# shield_v5.net
KiCad netlist of a schematic drawn in EAGLE
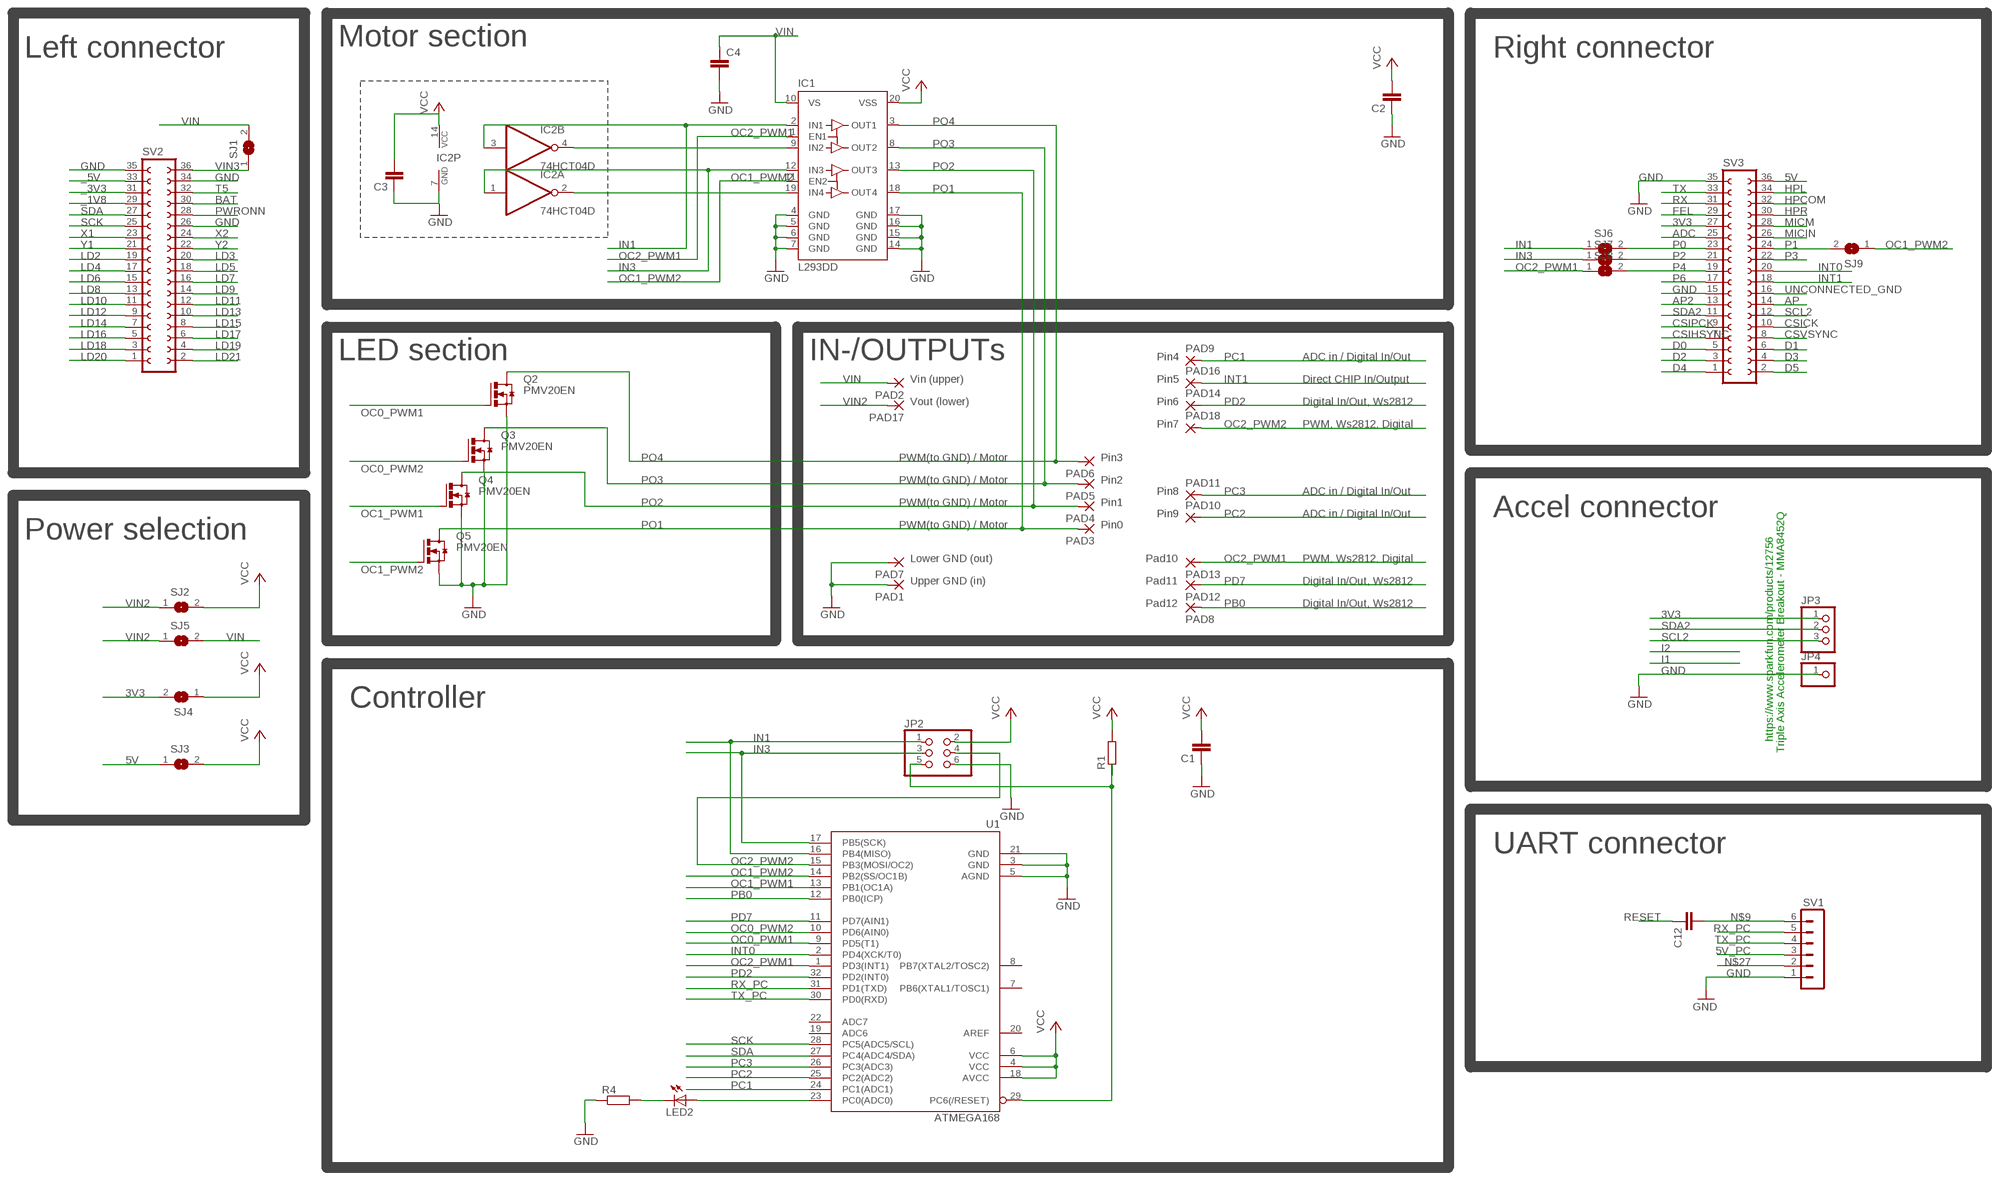
[diagram p0: schematic, sheet 1]

(export (version "E")
  (design (tool "Eeschema 10.0.6"))
  (components
    (comp (ref "C1")
      (value "C-EUC0805")
      (footprint "eagle-import:C0805")
      (libsource (lib "eagle-import") (part "C-EUC0805"))
    )
    (comp (ref "C2")
      (value "C-EUC0805")
      (footprint "eagle-import:C0805")
      (libsource (lib "eagle-import") (part "C-EUC0805"))
    )
    (comp (ref "C3")
      (value "C-EUC0805")
      (footprint "eagle-import:C0805")
      (libsource (lib "eagle-import") (part "C-EUC0805"))
    )
    (comp (ref "C4")
      (value "C-EUC1210")
      (footprint "eagle-import:C1210")
      (libsource (lib "eagle-import") (part "C-EUC1210"))
    )
    (comp (ref "C12")
      (value "C-EUC1206")
      (footprint "eagle-import:C1206")
      (libsource (lib "eagle-import") (part "C-EUC1206"))
    )
    (comp (ref "IC1")
      (value "L293DD")
      (footprint "eagle-import:SO20")
      (libsource (lib "eagle-import") (part "L293DD"))
    )
    (comp (ref "IC2")
      (value "74HCT04D")
      (footprint "eagle-import:SO14")
      (libsource (lib "eagle-import") (part "7404DHCT"))
    )
    (comp (ref "JP2")
      (value "PINHD-2X3")
      (footprint "eagle-import:2X03")
      (libsource (lib "eagle-import") (part "PINHD-2X3"))
    )
    (comp (ref "JP3")
      (value "PINHD-1X3")
      (footprint "eagle-import:1X03")
      (libsource (lib "eagle-import") (part "PINHD-1X3"))
    )
    (comp (ref "JP4")
      (value "PINHD-1X1")
      (footprint "eagle-import:1X01")
      (libsource (lib "eagle-import") (part "PINHD-1X1"))
    )
    (comp (ref "LED2")
      (value "LEDCHIP-LED0805")
      (footprint "eagle-import:CHIP-LED0805")
      (libsource (lib "eagle-import") (part "LEDCHIP-LED0805"))
    )
    (comp (ref "PAD1")
      (value "3,17/1,3")
      (footprint "eagle-import:3,17_1,3")
      (libsource (lib "eagle-import") (part "3,17/1,3"))
    )
    (comp (ref "PAD2")
      (value "3,17/1,3")
      (footprint "eagle-import:3,17_1,3")
      (libsource (lib "eagle-import") (part "3,17/1,3"))
    )
    (comp (ref "PAD3")
      (value "3,17/1,3")
      (footprint "eagle-import:3,17_1,3")
      (libsource (lib "eagle-import") (part "3,17/1,3"))
    )
    (comp (ref "PAD4")
      (value "3,17/1,3")
      (footprint "eagle-import:3,17_1,3")
      (libsource (lib "eagle-import") (part "3,17/1,3"))
    )
    (comp (ref "PAD5")
      (value "3,17/1,3")
      (footprint "eagle-import:3,17_1,3")
      (libsource (lib "eagle-import") (part "3,17/1,3"))
    )
    (comp (ref "PAD6")
      (value "3,17/1,3")
      (footprint "eagle-import:3,17_1,3")
      (libsource (lib "eagle-import") (part "3,17/1,3"))
    )
    (comp (ref "PAD7")
      (value "3,17/1,3")
      (footprint "eagle-import:3,17_1,3")
      (libsource (lib "eagle-import") (part "3,17/1,3"))
    )
    (comp (ref "PAD8")
      (value "WIREPADSMD1,27-254")
      (footprint "eagle-import:SMD1,27-2,54")
      (libsource (lib "eagle-import") (part "WIREPADSMD1,27-254"))
    )
    (comp (ref "PAD9")
      (value "3,17/1,3")
      (footprint "eagle-import:3,17_1,3")
      (libsource (lib "eagle-import") (part "3,17/1,3"))
    )
    (comp (ref "PAD10")
      (value "3,17/1,3")
      (footprint "eagle-import:3,17_1,3")
      (libsource (lib "eagle-import") (part "3,17/1,3"))
    )
    (comp (ref "PAD11")
      (value "3,17/1,3")
      (footprint "eagle-import:3,17_1,3")
      (libsource (lib "eagle-import") (part "3,17/1,3"))
    )
    (comp (ref "PAD12")
      (value "SMD2")
      (footprint "eagle-import:SMD1,27-2,54")
      (libsource (lib "eagle-import") (part "SMD2"))
    )
    (comp (ref "PAD13")
      (value "SMD2")
      (footprint "eagle-import:SMD1,27-2,54")
      (libsource (lib "eagle-import") (part "SMD2"))
    )
    (comp (ref "PAD14")
      (value "3,17/1,3")
      (footprint "eagle-import:3,17_1,3")
      (libsource (lib "eagle-import") (part "3,17/1,3"))
    )
    (comp (ref "PAD16")
      (value "3,17/1,3")
      (footprint "eagle-import:3,17_1,3")
      (libsource (lib "eagle-import") (part "3,17/1,3"))
    )
    (comp (ref "PAD17")
      (value "3,17/1,3")
      (footprint "eagle-import:3,17_1,3")
      (libsource (lib "eagle-import") (part "3,17/1,3"))
    )
    (comp (ref "PAD18")
      (value "3,17/1,3")
      (footprint "eagle-import:3,17_1,3")
      (libsource (lib "eagle-import") (part "3,17/1,3"))
    )
    (comp (ref "Q2")
      (value "PMV20EN")
      (footprint "eagle-import:SOT223")
      (libsource (lib "eagle-import") (part "NMOSFET_SMD_223"))
    )
    (comp (ref "Q3")
      (value "PMV20EN")
      (footprint "eagle-import:SOT223")
      (libsource (lib "eagle-import") (part "NMOSFET_SMD_223"))
    )
    (comp (ref "Q4")
      (value "PMV20EN")
      (footprint "eagle-import:SOT223")
      (libsource (lib "eagle-import") (part "NMOSFET_SMD_223"))
    )
    (comp (ref "Q5")
      (value "PMV20EN")
      (footprint "eagle-import:SOT223")
      (libsource (lib "eagle-import") (part "NMOSFET_SMD_223"))
    )
    (comp (ref "R1")
      (value "R-EU_M1206")
      (footprint "eagle-import:M1206")
      (libsource (lib "eagle-import") (part "R-EU_M1206"))
    )
    (comp (ref "R4")
      (value "R-EU_M1206")
      (footprint "eagle-import:M1206")
      (libsource (lib "eagle-import") (part "R-EU_M1206"))
    )
    (comp (ref "SJ1") (value "SJ") (footprint "eagle-import:SJ") (libsource (lib "eagle-import") (part "SJ")))
    (comp (ref "SJ2") (value "SJ") (footprint "eagle-import:SJ") (libsource (lib "eagle-import") (part "SJ")))
    (comp (ref "SJ3") (value "SJ") (footprint "eagle-import:SJ") (libsource (lib "eagle-import") (part "SJ")))
    (comp (ref "SJ4") (value "SJ") (footprint "eagle-import:SJ") (libsource (lib "eagle-import") (part "SJ")))
    (comp (ref "SJ5") (value "SJ") (footprint "eagle-import:SJ") (libsource (lib "eagle-import") (part "SJ")))
    (comp (ref "SJ6") (value "SJ") (footprint "eagle-import:SJ") (libsource (lib "eagle-import") (part "SJ")))
    (comp (ref "SJ7") (value "SJ") (footprint "eagle-import:SJ") (libsource (lib "eagle-import") (part "SJ")))
    (comp (ref "SJ8") (value "SJ") (footprint "eagle-import:SJ") (libsource (lib "eagle-import") (part "SJ")))
    (comp (ref "SJ9") (value "SJ") (footprint "eagle-import:SJ") (libsource (lib "eagle-import") (part "SJ")))
    (comp (ref "SV1")
      (value "MA06-1")
      (footprint "eagle-import:MA06-1")
      (libsource (lib "eagle-import") (part "MA06-1"))
    )
    (comp (ref "SV2")
      (value "FE18-2")
      (footprint "eagle-import:FE18-2")
      (libsource (lib "eagle-import") (part "FE18-2"))
    )
    (comp (ref "SV3")
      (value "FE18-2")
      (footprint "eagle-import:FE18-2")
      (libsource (lib "eagle-import") (part "FE18-2"))
    )
    (comp (ref "U1")
      (value "ATMEGA168")
      (footprint "eagle-import:TQFP32-08")
      (libsource (lib "eagle-import") (part "ATMEGA168"))
    )
  )
  (nets
    (net (code "1") (name "/3V3") (class "Default")
      (node (ref "JP3") (pin "1") (pinfunction "1_1") (pintype "passive"))
      (node (ref "SJ4") (pin "2") (pinfunction "2_2") (pintype "passive"))
      (node (ref "SV3") (pin "27") (pinfunction "27_27") (pintype "passive"))
    )
    (net (code "2") (name "/5V") (class "Default")
      (node (ref "SJ3") (pin "1") (pinfunction "1_1") (pintype "passive"))
      (node (ref "SV3") (pin "36") (pinfunction "36_36") (pintype "passive"))
    )
    (net (code "3") (name "/5V_PC") (class "Default")
      (node (ref "SV1") (pin "3") (pinfunction "3_3") (pintype "passive"))
    )
    (net (code "4") (name "/ADC") (class "Default")
      (node (ref "SV3") (pin "25") (pinfunction "25_25") (pintype "passive"))
    )
    (net (code "5") (name "/AP") (class "Default")
      (node (ref "SV3") (pin "14") (pinfunction "14_14") (pintype "passive"))
    )
    (net (code "6") (name "/AP2") (class "Default")
      (node (ref "SV3") (pin "13") (pinfunction "13_13") (pintype "passive"))
    )
    (net (code "7") (name "/BAT") (class "Default")
      (node (ref "SV2") (pin "30") (pinfunction "30_30") (pintype "passive"))
    )
    (net (code "8") (name "/CSICK") (class "Default")
      (node (ref "SV3") (pin "10") (pinfunction "10_10") (pintype "passive"))
    )
    (net (code "9") (name "/CSIHSYNC") (class "Default")
      (node (ref "SV3") (pin "7") (pinfunction "7_7") (pintype "passive"))
    )
    (net (code "10") (name "/CSIPCK") (class "Default")
      (node (ref "SV3") (pin "9") (pinfunction "9_9") (pintype "passive"))
    )
    (net (code "11") (name "/CSVSYNC") (class "Default")
      (node (ref "SV3") (pin "8") (pinfunction "8_8") (pintype "passive"))
    )
    (net (code "12") (name "/D0") (class "Default")
      (node (ref "SV3") (pin "5") (pinfunction "5_5") (pintype "passive"))
    )
    (net (code "13") (name "/D1") (class "Default")
      (node (ref "SV3") (pin "6") (pinfunction "6_6") (pintype "passive"))
    )
    (net (code "14") (name "/D2") (class "Default")
      (node (ref "SV3") (pin "3") (pinfunction "3_3") (pintype "passive"))
    )
    (net (code "15") (name "/D3") (class "Default")
      (node (ref "SV3") (pin "4") (pinfunction "4_4") (pintype "passive"))
    )
    (net (code "16") (name "/D4") (class "Default")
      (node (ref "SV3") (pin "1") (pinfunction "1_1") (pintype "passive"))
    )
    (net (code "17") (name "/D5") (class "Default")
      (node (ref "SV3") (pin "2") (pinfunction "2_2") (pintype "passive"))
    )
    (net (code "18") (name "/FEL") (class "Default")
      (node (ref "SV3") (pin "29") (pinfunction "29_29") (pintype "passive"))
    )
    (net (code "19") (name "/HPCOM") (class "Default")
      (node (ref "SV3") (pin "32") (pinfunction "32_32") (pintype "passive"))
    )
    (net (code "20") (name "/HPL") (class "Default")
      (node (ref "SV3") (pin "34") (pinfunction "34_34") (pintype "passive"))
    )
    (net (code "21") (name "/HPR") (class "Default")
      (node (ref "SV3") (pin "30") (pinfunction "30_30") (pintype "passive"))
    )
    (net (code "24") (name "/IN1") (class "Default")
      (node (ref "IC1") (pin "2") (pinfunction "IN1_2") (pintype "input"))
      (node (ref "IC2") (pin "3") (pinfunction "I_3") (pintype "input"))
      (node (ref "JP2") (pin "1") (pinfunction "1_1") (pintype "passive"))
      (node (ref "SJ6") (pin "1") (pinfunction "1_1") (pintype "passive"))
      (node (ref "U1") (pin "16") (pinfunction "PB4(MISO)_16") (pintype "bidirectional"))
    )
    (net (code "25") (name "/IN3") (class "Default")
      (node (ref "IC1") (pin "12") (pinfunction "IN3_12") (pintype "input"))
      (node (ref "IC2") (pin "1") (pinfunction "I_1") (pintype "input"))
      (node (ref "JP2") (pin "3") (pinfunction "3_3") (pintype "passive"))
      (node (ref "SJ7") (pin "1") (pinfunction "1_1") (pintype "passive"))
      (node (ref "U1") (pin "17") (pinfunction "PB5(SCK)_17") (pintype "bidirectional"))
    )
    (net (code "26") (name "/INT0") (class "Default")
      (node (ref "SV3") (pin "20") (pinfunction "20_20") (pintype "passive"))
      (node (ref "U1") (pin "2") (pinfunction "PD4(XCK/T0)_2") (pintype "bidirectional"))
    )
    (net (code "27") (name "/INT1") (class "Default")
      (node (ref "PAD16") (pin "1") (pinfunction "P_1") (pintype "passive"))
      (node (ref "SV3") (pin "18") (pinfunction "18_18") (pintype "passive"))
    )
    (net (code "28") (name "/LD2") (class "Default")
      (node (ref "SV2") (pin "19") (pinfunction "19_19") (pintype "passive"))
    )
    (net (code "29") (name "/LD3") (class "Default")
      (node (ref "SV2") (pin "20") (pinfunction "20_20") (pintype "passive"))
    )
    (net (code "30") (name "/LD4") (class "Default")
      (node (ref "SV2") (pin "17") (pinfunction "17_17") (pintype "passive"))
    )
    (net (code "31") (name "/LD5") (class "Default")
      (node (ref "SV2") (pin "18") (pinfunction "18_18") (pintype "passive"))
    )
    (net (code "32") (name "/LD6") (class "Default")
      (node (ref "SV2") (pin "15") (pinfunction "15_15") (pintype "passive"))
    )
    (net (code "33") (name "/LD7") (class "Default")
      (node (ref "SV2") (pin "16") (pinfunction "16_16") (pintype "passive"))
    )
    (net (code "34") (name "/LD8") (class "Default")
      (node (ref "SV2") (pin "13") (pinfunction "13_13") (pintype "passive"))
    )
    (net (code "35") (name "/LD9") (class "Default")
      (node (ref "SV2") (pin "14") (pinfunction "14_14") (pintype "passive"))
    )
    (net (code "36") (name "/LD10") (class "Default")
      (node (ref "SV2") (pin "11") (pinfunction "11_11") (pintype "passive"))
    )
    (net (code "37") (name "/LD11") (class "Default")
      (node (ref "SV2") (pin "12") (pinfunction "12_12") (pintype "passive"))
    )
    (net (code "38") (name "/LD12") (class "Default")
      (node (ref "SV2") (pin "9") (pinfunction "9_9") (pintype "passive"))
    )
    (net (code "39") (name "/LD13") (class "Default")
      (node (ref "SV2") (pin "10") (pinfunction "10_10") (pintype "passive"))
    )
    (net (code "40") (name "/LD14") (class "Default")
      (node (ref "SV2") (pin "7") (pinfunction "7_7") (pintype "passive"))
    )
    (net (code "41") (name "/LD15") (class "Default")
      (node (ref "SV2") (pin "8") (pinfunction "8_8") (pintype "passive"))
    )
    (net (code "42") (name "/LD16") (class "Default")
      (node (ref "SV2") (pin "5") (pinfunction "5_5") (pintype "passive"))
    )
    (net (code "43") (name "/LD17") (class "Default")
      (node (ref "SV2") (pin "6") (pinfunction "6_6") (pintype "passive"))
    )
    (net (code "44") (name "/LD18") (class "Default")
      (node (ref "SV2") (pin "3") (pinfunction "3_3") (pintype "passive"))
    )
    (net (code "45") (name "/LD19") (class "Default")
      (node (ref "SV2") (pin "4") (pinfunction "4_4") (pintype "passive"))
    )
    (net (code "46") (name "/LD20") (class "Default")
      (node (ref "SV2") (pin "1") (pinfunction "1_1") (pintype "passive"))
    )
    (net (code "47") (name "/LD21") (class "Default")
      (node (ref "SV2") (pin "2") (pinfunction "2_2") (pintype "passive"))
    )
    (net (code "48") (name "/MICIN") (class "Default")
      (node (ref "SV3") (pin "26") (pinfunction "26_26") (pintype "passive"))
    )
    (net (code "49") (name "/MICM") (class "Default")
      (node (ref "SV3") (pin "28") (pinfunction "28_28") (pintype "passive"))
    )
    (net (code "50") (name "/N$9") (class "Default")
      (node (ref "C12") (pin "2") (pinfunction "2_2") (pintype "passive"))
      (node (ref "SV1") (pin "6") (pinfunction "6_6") (pintype "passive"))
    )
    (net (code "51") (name "/N$27") (class "Default")
      (node (ref "SV1") (pin "2") (pinfunction "2_2") (pintype "passive"))
    )
    (net (code "52") (name "/OC0_PWM1") (class "Default")
      (node (ref "Q2") (pin "1") (pinfunction "G_1") (pintype "passive"))
      (node (ref "U1") (pin "9") (pinfunction "PD5(T1)_9") (pintype "bidirectional"))
    )
    (net (code "53") (name "/OC0_PWM2") (class "Default")
      (node (ref "Q3") (pin "1") (pinfunction "G_1") (pintype "passive"))
      (node (ref "U1") (pin "10") (pinfunction "PD6(AIN0)_10") (pintype "bidirectional"))
    )
    (net (code "54") (name "/OC1_PWM1") (class "Default")
      (node (ref "Q4") (pin "1") (pinfunction "G_1") (pintype "passive"))
      (node (ref "U1") (pin "13") (pinfunction "PB1(OC1A)_13") (pintype "bidirectional"))
    )
    (net (code "55") (name "/OC1_PWM2") (class "Default")
      (node (ref "IC1") (pin "11") (pinfunction "EN2_11") (pintype "input"))
      (node (ref "Q5") (pin "1") (pinfunction "G_1") (pintype "passive"))
      (node (ref "SJ9") (pin "1") (pinfunction "1_1") (pintype "passive"))
      (node (ref "U1") (pin "14") (pinfunction "PB2(SS/OC1B)_14") (pintype "bidirectional"))
    )
    (net (code "56") (name "/OC2_PWM1") (class "Default")
      (node (ref "IC1") (pin "1") (pinfunction "EN1_1") (pintype "input"))
      (node (ref "PAD13") (pin "1") (pinfunction "P_1") (pintype "passive"))
      (node (ref "SJ8") (pin "1") (pinfunction "1_1") (pintype "passive"))
      (node (ref "U1") (pin "1") (pinfunction "PD3(INT1)_1") (pintype "bidirectional"))
    )
    (net (code "57") (name "/OC2_PWM2") (class "Default")
      (node (ref "JP2") (pin "4") (pinfunction "4_4") (pintype "passive"))
      (node (ref "PAD18") (pin "1") (pinfunction "P_1") (pintype "passive"))
      (node (ref "U1") (pin "15") (pinfunction "PB3(MOSI/OC2)_15") (pintype "bidirectional"))
    )
    (net (code "58") (name "/P0") (class "Default")
      (node (ref "SJ6") (pin "2") (pinfunction "2_2") (pintype "passive"))
      (node (ref "SV3") (pin "23") (pinfunction "23_23") (pintype "passive"))
    )
    (net (code "59") (name "/P1") (class "Default")
      (node (ref "SJ9") (pin "2") (pinfunction "2_2") (pintype "passive"))
      (node (ref "SV3") (pin "24") (pinfunction "24_24") (pintype "passive"))
    )
    (net (code "60") (name "/P2") (class "Default")
      (node (ref "SJ7") (pin "2") (pinfunction "2_2") (pintype "passive"))
      (node (ref "SV3") (pin "21") (pinfunction "21_21") (pintype "passive"))
    )
    (net (code "61") (name "/P3") (class "Default")
      (node (ref "SV3") (pin "22") (pinfunction "22_22") (pintype "passive"))
    )
    (net (code "62") (name "/P4") (class "Default")
      (node (ref "SJ8") (pin "2") (pinfunction "2_2") (pintype "passive"))
      (node (ref "SV3") (pin "19") (pinfunction "19_19") (pintype "passive"))
    )
    (net (code "63") (name "/P6") (class "Default")
      (node (ref "SV3") (pin "17") (pinfunction "17_17") (pintype "passive"))
    )
    (net (code "64") (name "/PB0") (class "Default")
      (node (ref "PAD8") (pin "1") (pinfunction "P_1") (pintype "passive"))
      (node (ref "U1") (pin "12") (pinfunction "PB0(ICP)_12") (pintype "bidirectional"))
    )
    (net (code "65") (name "/PC1") (class "Default")
      (node (ref "PAD9") (pin "1") (pinfunction "P_1") (pintype "passive"))
      (node (ref "U1") (pin "24") (pinfunction "PC1(ADC1)_24") (pintype "bidirectional"))
    )
    (net (code "66") (name "/PC2") (class "Default")
      (node (ref "PAD10") (pin "1") (pinfunction "P_1") (pintype "passive"))
      (node (ref "U1") (pin "25") (pinfunction "PC2(ADC2)_25") (pintype "bidirectional"))
    )
    (net (code "67") (name "/PC3") (class "Default")
      (node (ref "PAD11") (pin "1") (pinfunction "P_1") (pintype "passive"))
      (node (ref "U1") (pin "26") (pinfunction "PC3(ADC3)_26") (pintype "bidirectional"))
    )
    (net (code "68") (name "/PD2") (class "Default")
      (node (ref "PAD14") (pin "1") (pinfunction "P_1") (pintype "passive"))
      (node (ref "U1") (pin "32") (pinfunction "PD2(INT0)_32") (pintype "bidirectional"))
    )
    (net (code "69") (name "/PD7") (class "Default")
      (node (ref "PAD12") (pin "1") (pinfunction "P_1") (pintype "passive"))
      (node (ref "U1") (pin "11") (pinfunction "PD7(AIN1)_11") (pintype "bidirectional"))
    )
    (net (code "70") (name "/PO1") (class "Default")
      (node (ref "IC1") (pin "18") (pinfunction "OUT4_18") (pintype "output"))
      (node (ref "PAD3") (pin "1") (pinfunction "P_1") (pintype "passive"))
      (node (ref "Q5") (pin "2") (pinfunction "D_2") (pintype "passive"))
      (node (ref "Q5") (pin "4") (pinfunction "D_4") (pintype "passive"))
    )
    (net (code "71") (name "/PO2") (class "Default")
      (node (ref "IC1") (pin "13") (pinfunction "OUT3_13") (pintype "output"))
      (node (ref "PAD4") (pin "1") (pinfunction "P_1") (pintype "passive"))
      (node (ref "Q4") (pin "2") (pinfunction "D_2") (pintype "passive"))
      (node (ref "Q4") (pin "4") (pinfunction "D_4") (pintype "passive"))
    )
    (net (code "72") (name "/PO3") (class "Default")
      (node (ref "IC1") (pin "8") (pinfunction "OUT2_8") (pintype "output"))
      (node (ref "PAD5") (pin "1") (pinfunction "P_1") (pintype "passive"))
      (node (ref "Q3") (pin "2") (pinfunction "D_2") (pintype "passive"))
      (node (ref "Q3") (pin "4") (pinfunction "D_4") (pintype "passive"))
    )
    (net (code "73") (name "/PO4") (class "Default")
      (node (ref "IC1") (pin "3") (pinfunction "OUT1_3") (pintype "output"))
      (node (ref "PAD6") (pin "1") (pinfunction "P_1") (pintype "passive"))
      (node (ref "Q2") (pin "2") (pinfunction "D_2") (pintype "passive"))
      (node (ref "Q2") (pin "4") (pinfunction "D_4") (pintype "passive"))
    )
    (net (code "74") (name "/PWRONN") (class "Default")
      (node (ref "SV2") (pin "28") (pinfunction "28_28") (pintype "passive"))
    )
    (net (code "75") (name "/RESET") (class "Default")
      (node (ref "C12") (pin "1") (pinfunction "1_1") (pintype "passive"))
      (node (ref "JP2") (pin "5") (pinfunction "5_5") (pintype "passive"))
      (node (ref "R1") (pin "1") (pinfunction "1_1") (pintype "passive"))
      (node (ref "U1") (pin "29") (pinfunction "PC6(/RESET)_29") (pintype "bidirectional"))
    )
    (net (code "76") (name "/RX") (class "Default")
      (node (ref "SV3") (pin "31") (pinfunction "31_31") (pintype "passive"))
    )
    (net (code "77") (name "/RX_PC") (class "Default")
      (node (ref "SV1") (pin "5") (pinfunction "5_5") (pintype "passive"))
      (node (ref "U1") (pin "31") (pinfunction "PD1(TXD)_31") (pintype "bidirectional"))
    )
    (net (code "78") (name "/SCK") (class "Default")
      (node (ref "SV2") (pin "25") (pinfunction "25_25") (pintype "passive"))
      (node (ref "U1") (pin "28") (pinfunction "PC5(ADC5/SCL)_28") (pintype "bidirectional"))
    )
    (net (code "79") (name "/SCL2") (class "Default")
      (node (ref "JP3") (pin "3") (pinfunction "3_3") (pintype "passive"))
      (node (ref "SV3") (pin "12") (pinfunction "12_12") (pintype "passive"))
    )
    (net (code "80") (name "/SDA") (class "Default")
      (node (ref "SV2") (pin "27") (pinfunction "27_27") (pintype "passive"))
      (node (ref "U1") (pin "27") (pinfunction "PC4(ADC4/SDA)_27") (pintype "bidirectional"))
    )
    (net (code "81") (name "/SDA2") (class "Default")
      (node (ref "JP3") (pin "2") (pinfunction "2_2") (pintype "passive"))
      (node (ref "SV3") (pin "11") (pinfunction "11_11") (pintype "passive"))
    )
    (net (code "82") (name "/T5") (class "Default")
      (node (ref "SV2") (pin "32") (pinfunction "32_32") (pintype "passive"))
    )
    (net (code "83") (name "/TX") (class "Default")
      (node (ref "SV3") (pin "33") (pinfunction "33_33") (pintype "passive"))
    )
    (net (code "84") (name "/TX_PC") (class "Default")
      (node (ref "SV1") (pin "4") (pinfunction "4_4") (pintype "passive"))
      (node (ref "U1") (pin "30") (pinfunction "PD0(RXD)_30") (pintype "bidirectional"))
    )
    (net (code "85") (name "/UNCONNECTED_GND") (class "Default")
      (node (ref "SV3") (pin "16") (pinfunction "16_16") (pintype "passive"))
    )
    (net (code "86") (name "/VIN") (class "Default")
      (node (ref "C4") (pin "1") (pinfunction "1_1") (pintype "passive"))
      (node (ref "IC1") (pin "10") (pinfunction "VS_10") (pintype "power_in"))
      (node (ref "PAD2") (pin "1") (pinfunction "P_1") (pintype "passive"))
      (node (ref "SJ1") (pin "2") (pinfunction "2_2") (pintype "passive"))
      (node (ref "SJ5") (pin "2") (pinfunction "2_2") (pintype "passive"))
    )
    (net (code "87") (name "/VIN2") (class "Default")
      (node (ref "PAD17") (pin "1") (pinfunction "P_1") (pintype "passive"))
      (node (ref "SJ2") (pin "1") (pinfunction "1_1") (pintype "passive"))
      (node (ref "SJ5") (pin "1") (pinfunction "1_1") (pintype "passive"))
    )
    (net (code "88") (name "/VIN3") (class "Default")
      (node (ref "SJ1") (pin "1") (pinfunction "1_1") (pintype "passive"))
      (node (ref "SV2") (pin "36") (pinfunction "36_36") (pintype "passive"))
    )
    (net (code "89") (name "/X1") (class "Default")
      (node (ref "SV2") (pin "23") (pinfunction "23_23") (pintype "passive"))
    )
    (net (code "90") (name "/X2") (class "Default")
      (node (ref "SV2") (pin "24") (pinfunction "24_24") (pintype "passive"))
    )
    (net (code "91") (name "/Y1") (class "Default")
      (node (ref "SV2") (pin "21") (pinfunction "21_21") (pintype "passive"))
    )
    (net (code "92") (name "/Y2") (class "Default")
      (node (ref "SV2") (pin "22") (pinfunction "22_22") (pintype "passive"))
    )
    (net (code "93") (name "/_1V8") (class "Default")
      (node (ref "SV2") (pin "29") (pinfunction "29_29") (pintype "passive"))
    )
    (net (code "94") (name "/_3V3") (class "Default")
      (node (ref "SV2") (pin "31") (pinfunction "31_31") (pintype "passive"))
    )
    (net (code "95") (name "/_5V") (class "Default")
      (node (ref "SV2") (pin "33") (pinfunction "33_33") (pintype "passive"))
    )
    (net (code "96") (name "GND") (class "Default")
      (node (ref "C1") (pin "1") (pinfunction "1_1") (pintype "passive"))
      (node (ref "C2") (pin "1") (pinfunction "1_1") (pintype "passive"))
      (node (ref "C3") (pin "1") (pinfunction "1_1") (pintype "passive"))
      (node (ref "C4") (pin "2") (pinfunction "2_2") (pintype "passive"))
      (node (ref "IC1") (pin "14") (pinfunction "GND_14") (pintype "power_in"))
      (node (ref "IC1") (pin "15") (pinfunction "GND_15") (pintype "power_in"))
      (node (ref "IC1") (pin "16") (pinfunction "GND_16") (pintype "power_in"))
      (node (ref "IC1") (pin "17") (pinfunction "GND_17") (pintype "power_in"))
      (node (ref "IC1") (pin "4") (pinfunction "GND_4") (pintype "power_in"))
      (node (ref "IC1") (pin "5") (pinfunction "GND_5") (pintype "power_in"))
      (node (ref "IC1") (pin "6") (pinfunction "GND_6") (pintype "power_in"))
      (node (ref "IC1") (pin "7") (pinfunction "GND_7") (pintype "power_in"))
      (node (ref "IC2") (pin "7") (pinfunction "GND_7") (pintype "power_in"))
      (node (ref "JP2") (pin "6") (pinfunction "6_6") (pintype "passive"))
      (node (ref "JP4") (pin "1") (pinfunction "1_1") (pintype "passive"))
      (node (ref "PAD1") (pin "1") (pinfunction "P_1") (pintype "passive"))
      (node (ref "PAD7") (pin "1") (pinfunction "P_1") (pintype "passive"))
      (node (ref "Q2") (pin "3") (pinfunction "S_3") (pintype "passive"))
      (node (ref "Q3") (pin "3") (pinfunction "S_3") (pintype "passive"))
      (node (ref "Q4") (pin "3") (pinfunction "S_3") (pintype "passive"))
      (node (ref "Q5") (pin "3") (pinfunction "S_3") (pintype "passive"))
      (node (ref "R4") (pin "1") (pinfunction "1_1") (pintype "passive"))
      (node (ref "SV1") (pin "1") (pinfunction "1_1") (pintype "passive"))
      (node (ref "SV2") (pin "26") (pinfunction "26_26") (pintype "passive"))
      (node (ref "SV2") (pin "34") (pinfunction "34_34") (pintype "passive"))
      (node (ref "SV2") (pin "35") (pinfunction "35_35") (pintype "passive"))
      (node (ref "SV3") (pin "15") (pinfunction "15_15") (pintype "passive"))
      (node (ref "SV3") (pin "35") (pinfunction "35_35") (pintype "passive"))
      (node (ref "U1") (pin "21") (pinfunction "GND_21") (pintype "bidirectional"))
      (node (ref "U1") (pin "3") (pinfunction "GND_3") (pintype "bidirectional"))
      (node (ref "U1") (pin "5") (pinfunction "AGND_5") (pintype "bidirectional"))
    )
    (net (code "97") (name "Net-(IC1-IN2)") (class "Default")
      (node (ref "IC1") (pin "9") (pinfunction "IN2_9") (pintype "input"))
      (node (ref "IC2") (pin "4") (pinfunction "O_4") (pintype "output"))
    )
    (net (code "98") (name "Net-(IC1-IN4)") (class "Default")
      (node (ref "IC1") (pin "19") (pinfunction "IN4_19") (pintype "input"))
      (node (ref "IC2") (pin "2") (pinfunction "O_2") (pintype "output"))
    )
    (net (code "99") (name "Net-(LED2-PadC)") (class "Default")
      (node (ref "LED2") (pin "C") (pinfunction "C_C") (pintype "passive"))
      (node (ref "R4") (pin "2") (pinfunction "2_2") (pintype "passive"))
    )
    (net (code "100") (name "Net-(U1-PC0(ADC0))") (class "Default")
      (node (ref "LED2") (pin "A") (pinfunction "A_A") (pintype "passive"))
      (node (ref "U1") (pin "23") (pinfunction "PC0(ADC0)_23") (pintype "bidirectional"))
    )
    (net (code "101") (name "VCC") (class "Default")
      (node (ref "C1") (pin "2") (pinfunction "2_2") (pintype "passive"))
      (node (ref "C2") (pin "2") (pinfunction "2_2") (pintype "passive"))
      (node (ref "C3") (pin "2") (pinfunction "2_2") (pintype "passive"))
      (node (ref "IC1") (pin "20") (pinfunction "VSS_20") (pintype "power_in"))
      (node (ref "IC2") (pin "14") (pinfunction "VCC_14") (pintype "power_in"))
      (node (ref "JP2") (pin "2") (pinfunction "2_2") (pintype "passive"))
      (node (ref "R1") (pin "2") (pinfunction "2_2") (pintype "passive"))
      (node (ref "SJ2") (pin "2") (pinfunction "2_2") (pintype "passive"))
      (node (ref "SJ3") (pin "2") (pinfunction "2_2") (pintype "passive"))
      (node (ref "SJ4") (pin "1") (pinfunction "1_1") (pintype "passive"))
      (node (ref "U1") (pin "18") (pinfunction "AVCC_18") (pintype "bidirectional"))
      (node (ref "U1") (pin "4") (pinfunction "VCC_4") (pintype "bidirectional"))
      (node (ref "U1") (pin "6") (pinfunction "VCC_6") (pintype "bidirectional"))
    )
    (net (code "102") (name "unconnected-(U1-ADC6-Pad19)") (class "Default")
      (node (ref "U1") (pin "19") (pinfunction "ADC6_19") (pintype "bidirectional"))
    )
    (net (code "103") (name "unconnected-(U1-ADC7-Pad22)") (class "Default")
      (node (ref "U1") (pin "22") (pinfunction "ADC7_22") (pintype "bidirectional"))
    )
    (net (code "104") (name "unconnected-(U1-AREF-Pad20)") (class "Default")
      (node (ref "U1") (pin "20") (pinfunction "AREF_20") (pintype "bidirectional"))
    )
    (net (code "105") (name "unconnected-(U1-PB6(XTAL1{slash}TOSC1)-Pad7)") (class "Default")
      (node (ref "U1") (pin "7") (pinfunction "PB6(XTAL1/TOSC1)_7") (pintype "bidirectional"))
    )
    (net (code "106") (name "unconnected-(U1-PB7(XTAL2{slash}TOSC2)-Pad8)") (class "Default")
      (node (ref "U1") (pin "8") (pinfunction "PB7(XTAL2/TOSC2)_8") (pintype "bidirectional"))
    )
  )
)
